# Motor.net
KiCad netlist of a schematic drawn in Altium Designer
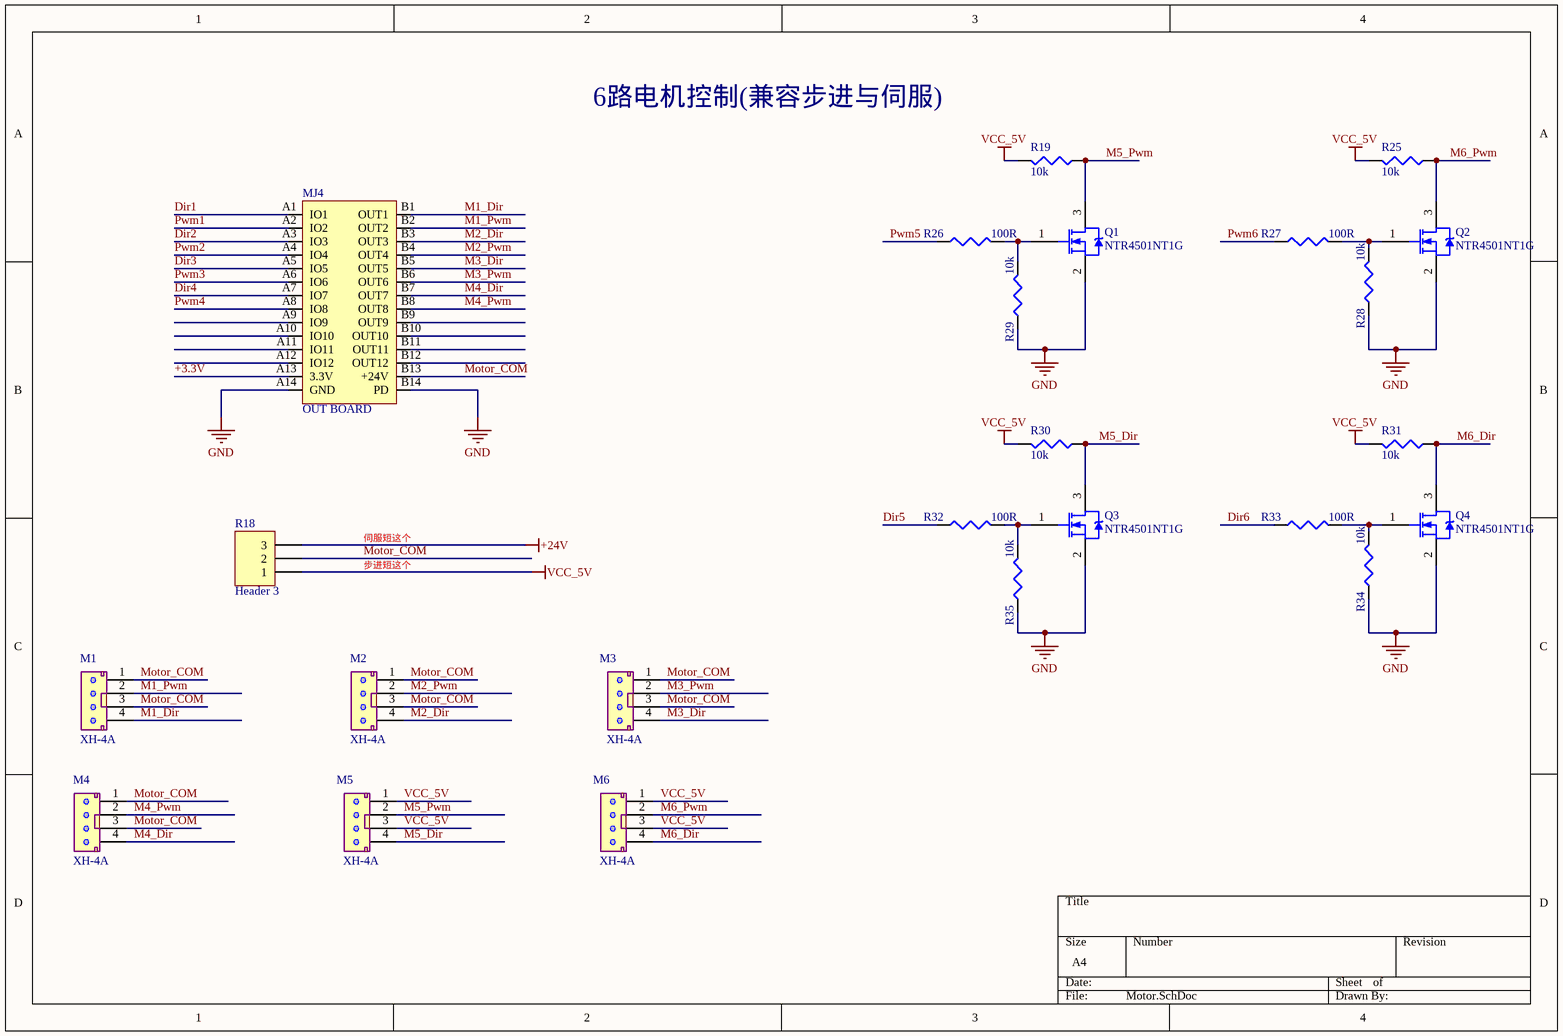
[diagram p0: Motor.SchDoc]

(export (version "E")
  (design (tool "Eeschema 10.0.6"))
  (components
    (comp (ref "M1") (value "XH-4A") (footprint "CN4-3.5") (libsource (lib "元件库-标准") (part "CON4")))
    (comp (ref "M2") (value "XH-4A") (footprint "CN4-3.5") (libsource (lib "元件库-标准") (part "CON4")))
    (comp (ref "M3") (value "XH-4A") (footprint "CN4-3.5") (libsource (lib "元件库-标准") (part "CON4")))
    (comp (ref "M4") (value "XH-4A") (footprint "CN4-3.5") (libsource (lib "元件库-标准") (part "CON4")))
    (comp (ref "M5") (value "XH-4A") (footprint "CN4-3.5") (libsource (lib "元件库-标准") (part "CON4")))
    (comp (ref "M6") (value "XH-4A") (footprint "CN4-3.5") (libsource (lib "元件库-标准") (part "CON4")))
    (comp (ref "MJ4")
      (value "OUT BOARD")
      (footprint "OUT BOARD")
      (libsource (lib "Block Board Library SCH") (part "J-OUTPUT"))
    )
    (comp (ref "Q1")
      (value "NTR4501NT1G")
      (footprint "SOT-23")
      (description "MOSFET N沟道")
      (libsource (lib "LGA") (part "MOSFET-N"))
    )
    (comp (ref "Q2")
      (value "NTR4501NT1G")
      (footprint "SOT-23")
      (description "MOSFET N沟道")
      (libsource (lib "LGA") (part "MOSFET-N"))
    )
    (comp (ref "Q3")
      (value "NTR4501NT1G")
      (footprint "SOT-23")
      (description "MOSFET N沟道")
      (libsource (lib "LGA") (part "MOSFET-N"))
    )
    (comp (ref "Q4")
      (value "NTR4501NT1G")
      (footprint "SOT-23")
      (description "MOSFET N沟道")
      (libsource (lib "LGA") (part "MOSFET-N"))
    )
    (comp (ref "R18")
      (value "Header 3")
      (footprint "3P-0603")
      (description "Header, 3-Pin")
      (fields (field (name "PUBLISHER") "Altium Limited"))
      (libsource (lib "Miscellaneous Connectors") (part "Header 3"))
    )
    (comp (ref "R19") (value "10k") (footprint "0603R") (libsource (lib "LGA") (part "RES1")))
    (comp (ref "R25") (value "10k") (footprint "0603R") (libsource (lib "LGA") (part "RES1")))
    (comp (ref "R26") (value "100R") (footprint "0603R") (libsource (lib "LGA") (part "RES1")))
    (comp (ref "R27") (value "100R") (footprint "0603R") (libsource (lib "LGA") (part "RES1")))
    (comp (ref "R28") (value "10k") (footprint "0603R") (libsource (lib "LGA") (part "RES1")))
    (comp (ref "R29") (value "10k") (footprint "0603R") (libsource (lib "LGA") (part "RES1")))
    (comp (ref "R30") (value "10k") (footprint "0603R") (libsource (lib "LGA") (part "RES1")))
    (comp (ref "R31") (value "10k") (footprint "0603R") (libsource (lib "LGA") (part "RES1")))
    (comp (ref "R32") (value "100R") (footprint "0603R") (libsource (lib "LGA") (part "RES1")))
    (comp (ref "R33") (value "100R") (footprint "0603R") (libsource (lib "LGA") (part "RES1")))
    (comp (ref "R34") (value "10k") (footprint "0603R") (libsource (lib "LGA") (part "RES1")))
    (comp (ref "R35") (value "10k") (footprint "0603R") (libsource (lib "LGA") (part "RES1")))
  )
  (nets
    (net (code "1") (name "+24V") (class "Default")
      (node (ref "R18") (pin "3") (pinfunction "3_3") (pintype "passive"))
    )
    (net (code "2") (name "/+3.3V") (class "Default")
      (node (ref "MJ4") (pin "A13") (pinfunction "3.3V_A13") (pintype "passive"))
    )
    (net (code "3") (name "/Dir1") (class "Default")
      (node (ref "MJ4") (pin "A1") (pinfunction "IO1_A1") (pintype "passive"))
    )
    (net (code "4") (name "/Dir2") (class "Default")
      (node (ref "MJ4") (pin "A3") (pinfunction "IO3_A3") (pintype "passive"))
    )
    (net (code "5") (name "/Dir3") (class "Default")
      (node (ref "MJ4") (pin "A5") (pinfunction "IO5_A5") (pintype "passive"))
    )
    (net (code "6") (name "/Dir4") (class "Default")
      (node (ref "MJ4") (pin "A7") (pinfunction "IO7_A7") (pintype "passive"))
    )
    (net (code "7") (name "/Dir5") (class "Default")
      (node (ref "R32") (pin "1") (pinfunction "1_1") (pintype "passive"))
    )
    (net (code "8") (name "/Dir6") (class "Default")
      (node (ref "R33") (pin "1") (pinfunction "1_1") (pintype "passive"))
    )
    (net (code "9") (name "/M1_Dir") (class "Default")
      (node (ref "M1") (pin "4") (pinfunction "4_4") (pintype "passive"))
      (node (ref "MJ4") (pin "B1") (pinfunction "OUT1_B1") (pintype "passive"))
    )
    (net (code "10") (name "/M1_Pwm") (class "Default")
      (node (ref "M1") (pin "2") (pinfunction "2_2") (pintype "passive"))
      (node (ref "MJ4") (pin "B2") (pinfunction "OUT2_B2") (pintype "passive"))
    )
    (net (code "11") (name "/M2_Dir") (class "Default")
      (node (ref "M2") (pin "4") (pinfunction "4_4") (pintype "passive"))
      (node (ref "MJ4") (pin "B3") (pinfunction "OUT3_B3") (pintype "passive"))
    )
    (net (code "12") (name "/M2_Pwm") (class "Default")
      (node (ref "M2") (pin "2") (pinfunction "2_2") (pintype "passive"))
      (node (ref "MJ4") (pin "B4") (pinfunction "OUT4_B4") (pintype "passive"))
    )
    (net (code "13") (name "/M3_Dir") (class "Default")
      (node (ref "M3") (pin "4") (pinfunction "4_4") (pintype "passive"))
      (node (ref "MJ4") (pin "B5") (pinfunction "OUT5_B5") (pintype "passive"))
    )
    (net (code "14") (name "/M3_Pwm") (class "Default")
      (node (ref "M3") (pin "2") (pinfunction "2_2") (pintype "passive"))
      (node (ref "MJ4") (pin "B6") (pinfunction "OUT6_B6") (pintype "passive"))
    )
    (net (code "15") (name "/M4_Dir") (class "Default")
      (node (ref "M4") (pin "4") (pinfunction "4_4") (pintype "passive"))
      (node (ref "MJ4") (pin "B7") (pinfunction "OUT7_B7") (pintype "passive"))
    )
    (net (code "16") (name "/M4_Pwm") (class "Default")
      (node (ref "M4") (pin "2") (pinfunction "2_2") (pintype "passive"))
      (node (ref "MJ4") (pin "B8") (pinfunction "OUT8_B8") (pintype "passive"))
    )
    (net (code "17") (name "/M5_Dir") (class "Default")
      (node (ref "M5") (pin "4") (pinfunction "4_4") (pintype "passive"))
      (node (ref "Q3") (pin "3") (pinfunction "D_3") (pintype "passive"))
      (node (ref "R30") (pin "1") (pinfunction "1_1") (pintype "passive"))
    )
    (net (code "18") (name "/M5_Pwm") (class "Default")
      (node (ref "M5") (pin "2") (pinfunction "2_2") (pintype "passive"))
      (node (ref "Q1") (pin "3") (pinfunction "D_3") (pintype "passive"))
      (node (ref "R19") (pin "1") (pinfunction "1_1") (pintype "passive"))
    )
    (net (code "19") (name "/M6_Dir") (class "Default")
      (node (ref "M6") (pin "4") (pinfunction "4_4") (pintype "passive"))
      (node (ref "Q4") (pin "3") (pinfunction "D_3") (pintype "passive"))
      (node (ref "R31") (pin "1") (pinfunction "1_1") (pintype "passive"))
    )
    (net (code "20") (name "/M6_Pwm") (class "Default")
      (node (ref "M6") (pin "2") (pinfunction "2_2") (pintype "passive"))
      (node (ref "Q2") (pin "3") (pinfunction "D_3") (pintype "passive"))
      (node (ref "R25") (pin "1") (pinfunction "1_1") (pintype "passive"))
    )
    (net (code "21") (name "/Motor_COM") (class "Default")
      (node (ref "M1") (pin "1") (pinfunction "1_1") (pintype "passive"))
      (node (ref "M1") (pin "3") (pinfunction "3_3") (pintype "passive"))
      (node (ref "M2") (pin "1") (pinfunction "1_1") (pintype "passive"))
      (node (ref "M2") (pin "3") (pinfunction "3_3") (pintype "passive"))
      (node (ref "M3") (pin "1") (pinfunction "1_1") (pintype "passive"))
      (node (ref "M3") (pin "3") (pinfunction "3_3") (pintype "passive"))
      (node (ref "M4") (pin "1") (pinfunction "1_1") (pintype "passive"))
      (node (ref "M4") (pin "3") (pinfunction "3_3") (pintype "passive"))
      (node (ref "MJ4") (pin "B13") (pinfunction "+24V_B13") (pintype "passive"))
      (node (ref "R18") (pin "2") (pinfunction "2_2") (pintype "passive"))
    )
    (net (code "22") (name "/Pwm1") (class "Default")
      (node (ref "MJ4") (pin "A2") (pinfunction "IO2_A2") (pintype "passive"))
    )
    (net (code "23") (name "/Pwm2") (class "Default")
      (node (ref "MJ4") (pin "A4") (pinfunction "IO4_A4") (pintype "passive"))
    )
    (net (code "24") (name "/Pwm3") (class "Default")
      (node (ref "MJ4") (pin "A6") (pinfunction "IO6_A6") (pintype "passive"))
    )
    (net (code "25") (name "/Pwm4") (class "Default")
      (node (ref "MJ4") (pin "A8") (pinfunction "IO8_A8") (pintype "passive"))
    )
    (net (code "26") (name "/Pwm5") (class "Default")
      (node (ref "R26") (pin "1") (pinfunction "1_1") (pintype "passive"))
    )
    (net (code "27") (name "/Pwm6") (class "Default")
      (node (ref "R27") (pin "1") (pinfunction "1_1") (pintype "passive"))
    )
    (net (code "28") (name "GND") (class "Default")
      (node (ref "MJ4") (pin "A14") (pinfunction "GND_A14") (pintype "passive"))
      (node (ref "MJ4") (pin "B14") (pinfunction "PD_B14") (pintype "passive"))
      (node (ref "Q1") (pin "2") (pinfunction "S_2") (pintype "passive"))
      (node (ref "Q2") (pin "2") (pinfunction "S_2") (pintype "passive"))
      (node (ref "Q3") (pin "2") (pinfunction "S_2") (pintype "passive"))
      (node (ref "Q4") (pin "2") (pinfunction "S_2") (pintype "passive"))
      (node (ref "R28") (pin "1") (pinfunction "1_1") (pintype "passive"))
      (node (ref "R29") (pin "1") (pinfunction "1_1") (pintype "passive"))
      (node (ref "R34") (pin "1") (pinfunction "1_1") (pintype "passive"))
      (node (ref "R35") (pin "1") (pinfunction "1_1") (pintype "passive"))
    )
    (net (code "29") (name "Net-(Q1-G)") (class "Default")
      (node (ref "Q1") (pin "1") (pinfunction "G_1") (pintype "passive"))
      (node (ref "R26") (pin "2") (pinfunction "2_2") (pintype "passive"))
      (node (ref "R29") (pin "2") (pinfunction "2_2") (pintype "passive"))
    )
    (net (code "30") (name "Net-(Q2-G)") (class "Default")
      (node (ref "Q2") (pin "1") (pinfunction "G_1") (pintype "passive"))
      (node (ref "R27") (pin "2") (pinfunction "2_2") (pintype "passive"))
      (node (ref "R28") (pin "2") (pinfunction "2_2") (pintype "passive"))
    )
    (net (code "31") (name "Net-(Q3-G)") (class "Default")
      (node (ref "Q3") (pin "1") (pinfunction "G_1") (pintype "passive"))
      (node (ref "R32") (pin "2") (pinfunction "2_2") (pintype "passive"))
      (node (ref "R35") (pin "2") (pinfunction "2_2") (pintype "passive"))
    )
    (net (code "32") (name "Net-(Q4-G)") (class "Default")
      (node (ref "Q4") (pin "1") (pinfunction "G_1") (pintype "passive"))
      (node (ref "R33") (pin "2") (pinfunction "2_2") (pintype "passive"))
      (node (ref "R34") (pin "2") (pinfunction "2_2") (pintype "passive"))
    )
    (net (code "33") (name "VCC_5V") (class "Default")
      (node (ref "M5") (pin "1") (pinfunction "1_1") (pintype "passive"))
      (node (ref "M5") (pin "3") (pinfunction "3_3") (pintype "passive"))
      (node (ref "M6") (pin "1") (pinfunction "1_1") (pintype "passive"))
      (node (ref "M6") (pin "3") (pinfunction "3_3") (pintype "passive"))
      (node (ref "R18") (pin "1") (pinfunction "1_1") (pintype "passive"))
      (node (ref "R19") (pin "2") (pinfunction "2_2") (pintype "passive"))
      (node (ref "R25") (pin "2") (pinfunction "2_2") (pintype "passive"))
      (node (ref "R30") (pin "2") (pinfunction "2_2") (pintype "passive"))
      (node (ref "R31") (pin "2") (pinfunction "2_2") (pintype "passive"))
    )
    (net (code "34") (name "unconnected-(MJ4-IO9-PadA9)") (class "Default")
      (node (ref "MJ4") (pin "A9") (pinfunction "IO9_A9") (pintype "passive"))
    )
    (net (code "35") (name "unconnected-(MJ4-IO10-PadA10)") (class "Default")
      (node (ref "MJ4") (pin "A10") (pinfunction "IO10_A10") (pintype "passive"))
    )
    (net (code "36") (name "unconnected-(MJ4-IO11-PadA11)") (class "Default")
      (node (ref "MJ4") (pin "A11") (pinfunction "IO11_A11") (pintype "passive"))
    )
    (net (code "37") (name "unconnected-(MJ4-IO12-PadA12)") (class "Default")
      (node (ref "MJ4") (pin "A12") (pinfunction "IO12_A12") (pintype "passive"))
    )
    (net (code "38") (name "unconnected-(MJ4-OUT9-PadB9)") (class "Default")
      (node (ref "MJ4") (pin "B9") (pinfunction "OUT9_B9") (pintype "passive"))
    )
    (net (code "39") (name "unconnected-(MJ4-OUT10-PadB10)") (class "Default")
      (node (ref "MJ4") (pin "B10") (pinfunction "OUT10_B10") (pintype "passive"))
    )
    (net (code "40") (name "unconnected-(MJ4-OUT11-PadB11)") (class "Default")
      (node (ref "MJ4") (pin "B11") (pinfunction "OUT11_B11") (pintype "passive"))
    )
    (net (code "41") (name "unconnected-(MJ4-OUT12-PadB12)") (class "Default")
      (node (ref "MJ4") (pin "B12") (pinfunction "OUT12_B12") (pintype "passive"))
    )
  )
)
